# 1wire-Thermocouple.net
KiCad netlist of a schematic drawn in Altium Designer
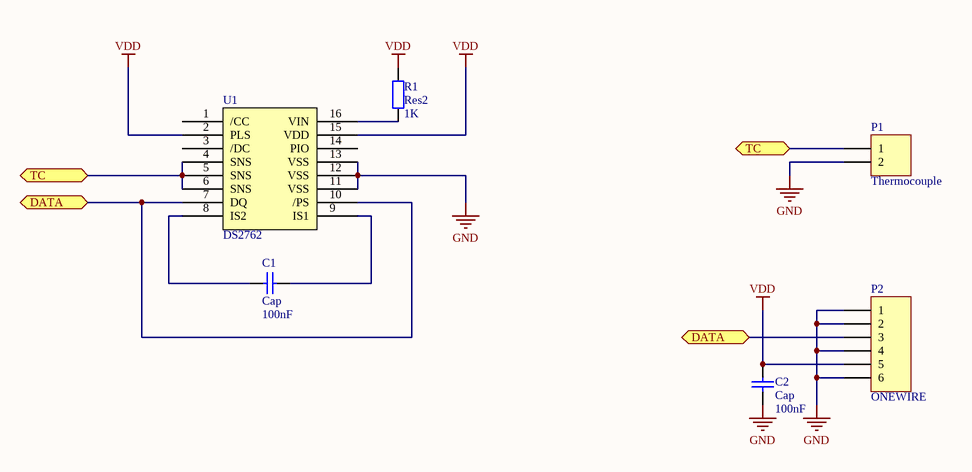
[diagram p0: 1wire-Thermocouple.SchDoc]

(export (version "E")
  (design (tool "Eeschema 10.0.6"))
  (components
    (comp (ref "C1")
      (value "Cap")
      (footprint "0603")
      (description "Capacitor")
      (fields (field (name "ALTIUM_VALUE") "100nF"))
      (libsource (lib "Miscellaneous Devices") (part "Cap"))
    )
    (comp (ref "C2")
      (value "Cap")
      (footprint "0603")
      (description "Capacitor")
      (fields (field (name "ALTIUM_VALUE") "100nF"))
      (libsource (lib "Miscellaneous Devices") (part "Cap"))
    )
    (comp (ref "P1")
      (value "Thermocouple")
      (footprint "PCC-SMP")
      (description "Header, 2-Pin")
      (fields (field (name "PUBLISHER") "Altium Limited"))
      (libsource (lib "Miscellaneous Connectors") (part "Header 2"))
    )
    (comp (ref "P2")
      (value "ONEWIRE")
      (footprint "CONN MOD JACK R/A 6P6C")
      (description "Header, 6-Pin")
      (libsource (lib "Miscellaneous Connectors") (part "Header 6"))
    )
    (comp (ref "R1")
      (value "Res2")
      (footprint "0603")
      (description "Resistor")
      (fields (field (name "ALTIUM_VALUE") "1K"))
      (libsource (lib "Miscellaneous Devices") (part "Res2"))
    )
    (comp (ref "U1")
      (value "DS2762")
      (footprint "TSSOP-16")
      (description "High-Precision Li+ Battery Monitor With Alerts")
      (libsource (lib "BrewBit") (part "DS2762"))
    )
  )
  (nets
    (net (code "1") (name "/DATA") (class "Default")
      (node (ref "P2") (pin "3") (pinfunction "3_3") (pintype "passive"))
      (node (ref "U1") (pin "10") (pinfunction "/PS_10") (pintype "passive"))
      (node (ref "U1") (pin "7") (pinfunction "DQ_7") (pintype "passive"))
    )
    (net (code "2") (name "/TC") (class "Default")
      (node (ref "P1") (pin "1") (pinfunction "1_1") (pintype "passive"))
      (node (ref "U1") (pin "4") (pinfunction "SNS_4") (pintype "passive"))
      (node (ref "U1") (pin "5") (pinfunction "SNS_5") (pintype "passive"))
      (node (ref "U1") (pin "6") (pinfunction "SNS_6") (pintype "passive"))
    )
    (net (code "3") (name "GND") (class "Default")
      (node (ref "C2") (pin "2") (pinfunction "2_2") (pintype "passive"))
      (node (ref "P1") (pin "2") (pinfunction "2_2") (pintype "passive"))
      (node (ref "P2") (pin "1") (pinfunction "1_1") (pintype "passive"))
      (node (ref "P2") (pin "2") (pinfunction "2_2") (pintype "passive"))
      (node (ref "P2") (pin "4") (pinfunction "4_4") (pintype "passive"))
      (node (ref "P2") (pin "6") (pinfunction "6_6") (pintype "passive"))
      (node (ref "U1") (pin "11") (pinfunction "VSS_11") (pintype "passive"))
      (node (ref "U1") (pin "12") (pinfunction "VSS_12") (pintype "passive"))
      (node (ref "U1") (pin "13") (pinfunction "VSS_13") (pintype "passive"))
    )
    (net (code "4") (name "Net-(U1-IS1)") (class "Default")
      (node (ref "C1") (pin "1") (pinfunction "1_1") (pintype "passive"))
      (node (ref "U1") (pin "9") (pinfunction "IS1_9") (pintype "passive"))
    )
    (net (code "5") (name "Net-(U1-IS2)") (class "Default")
      (node (ref "C1") (pin "2") (pinfunction "2_2") (pintype "passive"))
      (node (ref "U1") (pin "8") (pinfunction "IS2_8") (pintype "passive"))
    )
    (net (code "6") (name "Net-(U1-VIN)") (class "Default")
      (node (ref "R1") (pin "2") (pinfunction "2_2") (pintype "passive"))
      (node (ref "U1") (pin "16") (pinfunction "VIN_16") (pintype "passive"))
    )
    (net (code "7") (name "VDD") (class "Default")
      (node (ref "C2") (pin "1") (pinfunction "1_1") (pintype "passive"))
      (node (ref "P2") (pin "5") (pinfunction "5_5") (pintype "passive"))
      (node (ref "R1") (pin "1") (pinfunction "1_1") (pintype "passive"))
      (node (ref "U1") (pin "15") (pinfunction "VDD_15") (pintype "passive"))
      (node (ref "U1") (pin "2") (pinfunction "PLS_2") (pintype "passive"))
    )
    (net (code "8") (name "unconnected-(U1-PIO-Pad14)") (class "Default")
      (node (ref "U1") (pin "14") (pinfunction "PIO_14") (pintype "passive"))
    )
    (net (code "9") (name "unconnected-(U1-{slash}CC-Pad1)") (class "Default")
      (node (ref "U1") (pin "1") (pinfunction "/CC_1") (pintype "passive"))
    )
    (net (code "10") (name "unconnected-(U1-{slash}DC-Pad3)") (class "Default")
      (node (ref "U1") (pin "3") (pinfunction "/DC_3") (pintype "passive"))
    )
  )
)
